# main.net
KiCad netlist of a schematic drawn in EAGLE
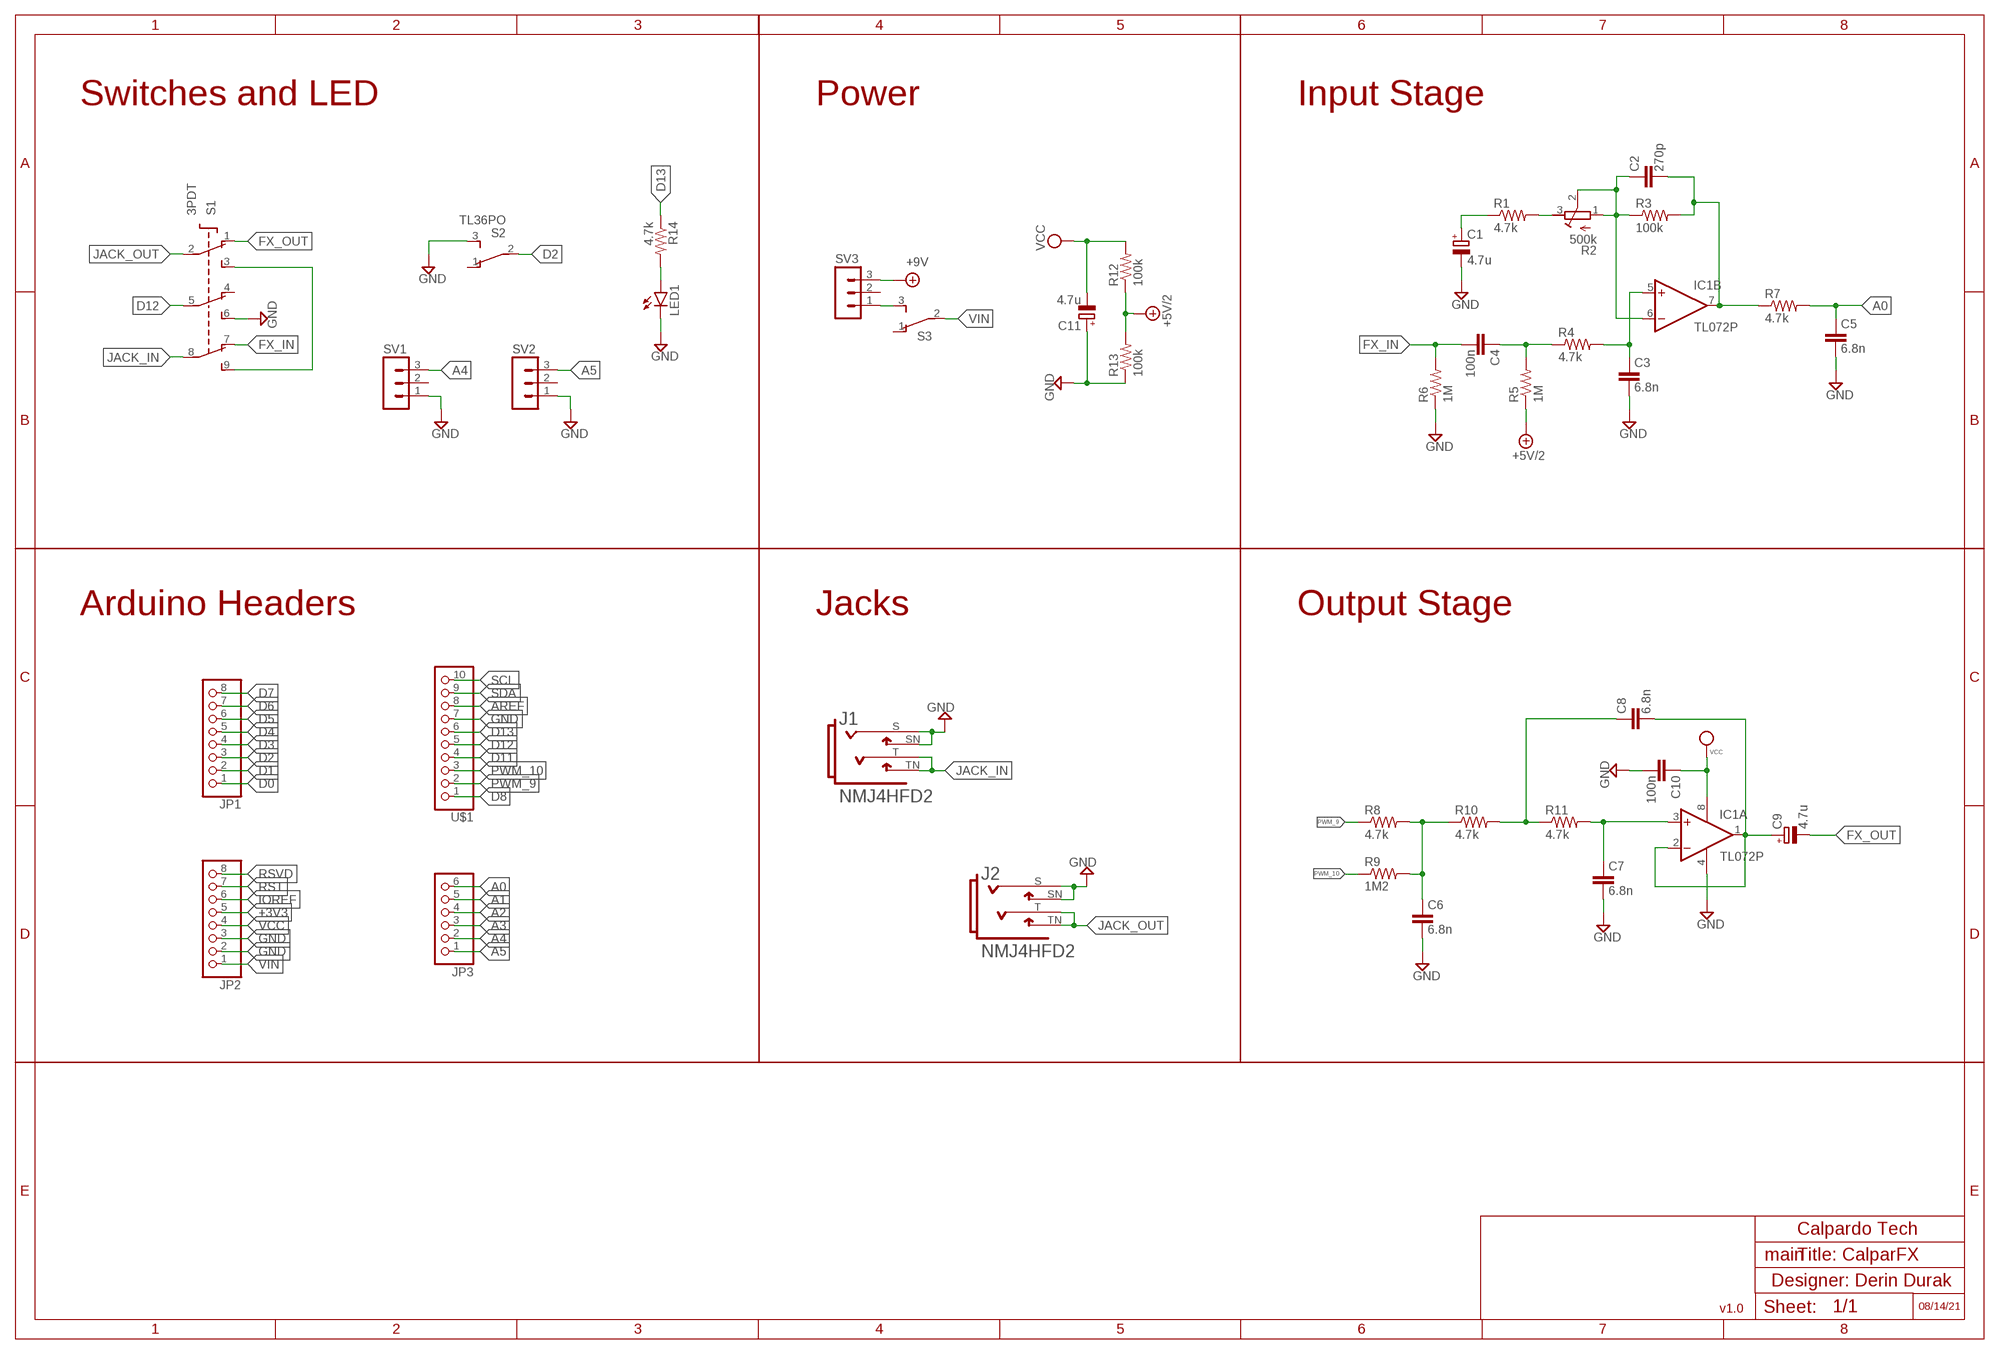
[diagram p0: schematic, sheet 1]

(export (version "E")
  (design (tool "Eeschema 10.0.6"))
  (components
    (comp (ref "C1")
      (value "4.7u")
      (footprint "eagle-import:E2-5")
      (libsource (lib "eagle-import") (part "CPOL-EUE2-5"))
    )
    (comp (ref "C2")
      (value "270p")
      (footprint "eagle-import:C025-024X044")
      (libsource (lib "eagle-import") (part "C-EU025-024X044"))
    )
    (comp (ref "C3")
      (value "6.8n")
      (footprint "eagle-import:C025-024X044")
      (libsource (lib "eagle-import") (part "C-EU025-024X044"))
    )
    (comp (ref "C4")
      (value "100n")
      (footprint "eagle-import:C025-024X044")
      (libsource (lib "eagle-import") (part "C-EU025-024X044"))
    )
    (comp (ref "C5")
      (value "6.8n")
      (footprint "eagle-import:C025-024X044")
      (libsource (lib "eagle-import") (part "C-EU025-024X044"))
    )
    (comp (ref "C6")
      (value "6.8n")
      (footprint "eagle-import:C025-024X044")
      (libsource (lib "eagle-import") (part "C-EU025-024X044"))
    )
    (comp (ref "C7")
      (value "6.8n")
      (footprint "eagle-import:C025-024X044")
      (libsource (lib "eagle-import") (part "C-EU025-024X044"))
    )
    (comp (ref "C8")
      (value "6.8n")
      (footprint "eagle-import:C025-024X044")
      (libsource (lib "eagle-import") (part "C-EU025-024X044"))
    )
    (comp (ref "C9")
      (value "4.7u")
      (footprint "eagle-import:E2-5")
      (libsource (lib "eagle-import") (part "CPOL-EUE2-5"))
    )
    (comp (ref "C10")
      (value "100n")
      (footprint "eagle-import:C025-024X044")
      (libsource (lib "eagle-import") (part "C-EU025-024X044"))
    )
    (comp (ref "C11")
      (value "4.7u")
      (footprint "eagle-import:E2-5")
      (libsource (lib "eagle-import") (part "CPOL-EUE2-5"))
    )
    (comp (ref "IC1")
      (value "TL072P")
      (footprint "eagle-import:DIL08")
      (libsource (lib "eagle-import") (part "TL072P"))
    )
    (comp (ref "J1")
      (value "NEUTRIK_NMJ4HFD2NEUTRIK_NMJ4HFD2_0_0")
      (footprint "eagle-import:NEUTRIK_NMJ4HFD2_0")
      (fields
        (field (name "MF") "Neutrik")
        (field (name "MOUSER_PART_NUMBER") "550-10201")
        (field (name "MPN") "NMJ4HFD2")
      )
      (libsource (lib "eagle-import") (part "NEUTRIK_NMJ4HFD2NEUTRIK_NMJ4HFD2_0_0"))
    )
    (comp (ref "J2")
      (value "NEUTRIK_NMJ4HFD2NEUTRIK_NMJ4HFD2_0_0")
      (footprint "eagle-import:NEUTRIK_NMJ4HFD2_0")
      (fields
        (field (name "MF") "Neutrik")
        (field (name "MOUSER_PART_NUMBER") "550-10201")
        (field (name "MPN") "NMJ4HFD2")
      )
      (libsource (lib "eagle-import") (part "NEUTRIK_NMJ4HFD2NEUTRIK_NMJ4HFD2_0_0"))
    )
    (comp (ref "JP1")
      (value "PINHD-1X8BIG")
      (footprint "eagle-import:1X08-BIG")
      (libsource (lib "eagle-import") (part "PINHD-1X8BIG"))
    )
    (comp (ref "JP2")
      (value "PINHD-1X8BIG")
      (footprint "eagle-import:1X08-BIG")
      (libsource (lib "eagle-import") (part "PINHD-1X8BIG"))
    )
    (comp (ref "JP3")
      (value "PINHD-1X6B")
      (footprint "eagle-import:1X06-BIG")
      (libsource (lib "eagle-import") (part "PINHD-1X6B"))
    )
    (comp (ref "LED1")
      (value "LED5MM")
      (footprint "eagle-import:LED5MM")
      (libsource (lib "eagle-import") (part "LED5MM"))
    )
    (comp (ref "R1")
      (value "4.7k")
      (footprint "eagle-import:0204_5")
      (libsource (lib "eagle-import") (part "R-US_0204/5"))
    )
    (comp (ref "R2")
      (value "500k")
      (footprint "eagle-import:RTRIM3296W")
      (libsource (lib "eagle-import") (part "R-TRIMM3296W"))
    )
    (comp (ref "R3")
      (value "100k")
      (footprint "eagle-import:0204_5")
      (libsource (lib "eagle-import") (part "R-US_0204/5"))
    )
    (comp (ref "R4")
      (value "4.7k")
      (footprint "eagle-import:0204_5")
      (libsource (lib "eagle-import") (part "R-US_0204/5"))
    )
    (comp (ref "R5")
      (value "1M")
      (footprint "eagle-import:0204_5")
      (libsource (lib "eagle-import") (part "R-US_0204/5"))
    )
    (comp (ref "R6")
      (value "1M")
      (footprint "eagle-import:0204_5")
      (libsource (lib "eagle-import") (part "R-US_0204/5"))
    )
    (comp (ref "R7")
      (value "4.7k")
      (footprint "eagle-import:0204_5")
      (libsource (lib "eagle-import") (part "R-US_0204/5"))
    )
    (comp (ref "R8")
      (value "4.7k")
      (footprint "eagle-import:0204_5")
      (libsource (lib "eagle-import") (part "R-US_0204/5"))
    )
    (comp (ref "R9")
      (value "1M2")
      (footprint "eagle-import:0204_5")
      (libsource (lib "eagle-import") (part "R-US_0204/5"))
    )
    (comp (ref "R10")
      (value "4.7k")
      (footprint "eagle-import:0204_5")
      (libsource (lib "eagle-import") (part "R-US_0204/5"))
    )
    (comp (ref "R11")
      (value "4.7k")
      (footprint "eagle-import:0204_5")
      (libsource (lib "eagle-import") (part "R-US_0204/5"))
    )
    (comp (ref "R12")
      (value "100k")
      (footprint "eagle-import:0204_5")
      (libsource (lib "eagle-import") (part "R-US_0204/5"))
    )
    (comp (ref "R13")
      (value "100k")
      (footprint "eagle-import:0204_5")
      (libsource (lib "eagle-import") (part "R-US_0204/5"))
    )
    (comp (ref "R14")
      (value "4.7k")
      (footprint "eagle-import:0204_5")
      (libsource (lib "eagle-import") (part "R-US_0204/5"))
    )
    (comp (ref "S1")
      (value "3PDT")
      (footprint "eagle-import:3PDT")
      (libsource (lib "eagle-import") (part "3PDT"))
    )
    (comp (ref "S2")
      (value "TL36PO")
      (footprint "eagle-import:TL3XPO")
      (libsource (lib "eagle-import") (part "TL36PO"))
    )
    (comp (ref "S3")
      (value "TL36PO")
      (footprint "eagle-import:TL3XPO")
      (libsource (lib "eagle-import") (part "TL36PO"))
    )
    (comp (ref "SV1")
      (value "MA03-1")
      (footprint "eagle-import:MA03-1")
      (libsource (lib "eagle-import") (part "MA03-1"))
    )
    (comp (ref "SV2")
      (value "MA03-1")
      (footprint "eagle-import:MA03-1")
      (libsource (lib "eagle-import") (part "MA03-1"))
    )
    (comp (ref "SV3")
      (value "MA03-1")
      (footprint "eagle-import:MA03-1")
      (libsource (lib "eagle-import") (part "MA03-1"))
    )
    (comp (ref "U$1")
      (value "PINHD-1X10")
      (footprint "eagle-import:1X10-BIG")
      (libsource (lib "eagle-import") (part "PINHD-1X10"))
    )
  )
  (nets
    (net (code "1") (name "+3V3") (class "Default")
      (node (ref "JP2") (pin "5") (pinfunction "5_5") (pintype "passive"))
    )
    (net (code "2") (name "+5V{slash}2") (class "Default")
      (node (ref "R12") (pin "1") (pinfunction "1_1") (pintype "passive"))
      (node (ref "R13") (pin "2") (pinfunction "2_2") (pintype "passive"))
      (node (ref "R5") (pin "1") (pinfunction "1_1") (pintype "passive"))
    )
    (net (code "3") (name "+9V") (class "Default")
      (node (ref "SV3") (pin "3") (pinfunction "3_3") (pintype "passive"))
    )
    (net (code "4") (name "A0") (class "Default")
      (node (ref "C5") (pin "1") (pinfunction "1_1") (pintype "passive"))
      (node (ref "JP3") (pin "6") (pinfunction "6_6") (pintype "passive"))
      (node (ref "R7") (pin "2") (pinfunction "2_2") (pintype "passive"))
    )
    (net (code "5") (name "A1") (class "Default")
      (node (ref "JP3") (pin "5") (pinfunction "5_5") (pintype "passive"))
    )
    (net (code "6") (name "A2") (class "Default")
      (node (ref "JP3") (pin "4") (pinfunction "4_4") (pintype "passive"))
    )
    (net (code "7") (name "A3") (class "Default")
      (node (ref "JP3") (pin "3") (pinfunction "3_3") (pintype "passive"))
    )
    (net (code "8") (name "A4") (class "Default")
      (node (ref "JP3") (pin "2") (pinfunction "2_2") (pintype "passive"))
      (node (ref "SV1") (pin "3") (pinfunction "3_3") (pintype "passive"))
    )
    (net (code "9") (name "A5") (class "Default")
      (node (ref "JP3") (pin "1") (pinfunction "1_1") (pintype "passive"))
      (node (ref "SV2") (pin "3") (pinfunction "3_3") (pintype "passive"))
    )
    (net (code "10") (name "AREF") (class "Default")
      (node (ref "U$1") (pin "8") (pinfunction "8_8") (pintype "passive"))
    )
    (net (code "11") (name "D0") (class "Default")
      (node (ref "JP1") (pin "1") (pinfunction "1_1") (pintype "passive"))
    )
    (net (code "12") (name "D1") (class "Default")
      (node (ref "JP1") (pin "2") (pinfunction "2_2") (pintype "passive"))
    )
    (net (code "13") (name "D2") (class "Default")
      (node (ref "JP1") (pin "3") (pinfunction "3_3") (pintype "passive"))
      (node (ref "S2") (pin "2") (pinfunction "P_2") (pintype "passive"))
    )
    (net (code "14") (name "D3") (class "Default")
      (node (ref "JP1") (pin "4") (pinfunction "4_4") (pintype "passive"))
    )
    (net (code "15") (name "D4") (class "Default")
      (node (ref "JP1") (pin "5") (pinfunction "5_5") (pintype "passive"))
    )
    (net (code "16") (name "D5") (class "Default")
      (node (ref "JP1") (pin "6") (pinfunction "6_6") (pintype "passive"))
    )
    (net (code "17") (name "D6") (class "Default")
      (node (ref "JP1") (pin "7") (pinfunction "7_7") (pintype "passive"))
    )
    (net (code "18") (name "D7") (class "Default")
      (node (ref "JP1") (pin "8") (pinfunction "8_8") (pintype "passive"))
    )
    (net (code "19") (name "D8") (class "Default")
      (node (ref "U$1") (pin "1") (pinfunction "1_1") (pintype "passive"))
    )
    (net (code "20") (name "D11") (class "Default")
      (node (ref "U$1") (pin "4") (pinfunction "4_4") (pintype "passive"))
    )
    (net (code "21") (name "D12") (class "Default")
      (node (ref "S1") (pin "5") (pinfunction "P2_5") (pintype "passive"))
      (node (ref "U$1") (pin "5") (pinfunction "5_5") (pintype "passive"))
    )
    (net (code "22") (name "D13") (class "Default")
      (node (ref "R14") (pin "1") (pinfunction "1_1") (pintype "passive"))
      (node (ref "U$1") (pin "6") (pinfunction "6_6") (pintype "passive"))
    )
    (net (code "23") (name "FX_IN") (class "Default")
      (node (ref "C4") (pin "2") (pinfunction "2_2") (pintype "passive"))
      (node (ref "R6") (pin "2") (pinfunction "2_2") (pintype "passive"))
      (node (ref "S1") (pin "7") (pinfunction "O3_7") (pintype "passive"))
    )
    (net (code "24") (name "FX_OUT") (class "Default")
      (node (ref "C9") (pin "-") (pinfunction "-_-") (pintype "passive"))
      (node (ref "S1") (pin "1") (pinfunction "O1_1") (pintype "passive"))
    )
    (net (code "25") (name "GND") (class "Default")
      (node (ref "C1") (pin "-") (pinfunction "-_-") (pintype "passive"))
      (node (ref "C10") (pin "2") (pinfunction "2_2") (pintype "passive"))
      (node (ref "C11") (pin "+") (pinfunction "+_+") (pintype "passive"))
      (node (ref "C3") (pin "2") (pinfunction "2_2") (pintype "passive"))
      (node (ref "C5") (pin "2") (pinfunction "2_2") (pintype "passive"))
      (node (ref "C6") (pin "2") (pinfunction "2_2") (pintype "passive"))
      (node (ref "C7") (pin "2") (pinfunction "2_2") (pintype "passive"))
      (node (ref "IC1") (pin "4") (pinfunction "V-_4") (pintype "power_in"))
      (node (ref "J1") (pin "S") (pinfunction "S_S") (pintype "passive"))
      (node (ref "J1") (pin "SN") (pinfunction "SN_SN") (pintype "passive"))
      (node (ref "J2") (pin "S") (pinfunction "S_S") (pintype "passive"))
      (node (ref "J2") (pin "SN") (pinfunction "SN_SN") (pintype "passive"))
      (node (ref "JP2") (pin "2") (pinfunction "2_2") (pintype "passive"))
      (node (ref "JP2") (pin "3") (pinfunction "3_3") (pintype "passive"))
      (node (ref "LED1") (pin "K") (pinfunction "C_K") (pintype "passive"))
      (node (ref "R13") (pin "1") (pinfunction "1_1") (pintype "passive"))
      (node (ref "R6") (pin "1") (pinfunction "1_1") (pintype "passive"))
      (node (ref "S1") (pin "6") (pinfunction "S2_6") (pintype "passive"))
      (node (ref "S2") (pin "3") (pinfunction "S_3") (pintype "passive"))
      (node (ref "SV1") (pin "1") (pinfunction "1_1") (pintype "passive"))
      (node (ref "SV2") (pin "1") (pinfunction "1_1") (pintype "passive"))
      (node (ref "U$1") (pin "7") (pinfunction "7_7") (pintype "passive"))
    )
    (net (code "26") (name "IOREF") (class "Default")
      (node (ref "JP2") (pin "6") (pinfunction "6_6") (pintype "passive"))
    )
    (net (code "27") (name "JACK_IN") (class "Default")
      (node (ref "J1") (pin "T") (pinfunction "T_T") (pintype "passive"))
      (node (ref "J1") (pin "TN") (pinfunction "TN_TN") (pintype "passive"))
      (node (ref "S1") (pin "8") (pinfunction "P3_8") (pintype "passive"))
    )
    (net (code "28") (name "JACK_OUT") (class "Default")
      (node (ref "J2") (pin "T") (pinfunction "T_T") (pintype "passive"))
      (node (ref "J2") (pin "TN") (pinfunction "TN_TN") (pintype "passive"))
      (node (ref "S1") (pin "2") (pinfunction "P1_2") (pintype "passive"))
    )
    (net (code "29") (name "Net-(C1-Pad+)") (class "Default")
      (node (ref "C1") (pin "+") (pinfunction "+_+") (pintype "passive"))
      (node (ref "R1") (pin "1") (pinfunction "1_1") (pintype "passive"))
    )
    (net (code "30") (name "Net-(C4-Pad1)") (class "Default")
      (node (ref "C4") (pin "1") (pinfunction "1_1") (pintype "passive"))
      (node (ref "R4") (pin "1") (pinfunction "1_1") (pintype "passive"))
      (node (ref "R5") (pin "2") (pinfunction "2_2") (pintype "passive"))
    )
    (net (code "31") (name "Net-(C6-Pad1)") (class "Default")
      (node (ref "C6") (pin "1") (pinfunction "1_1") (pintype "passive"))
      (node (ref "R10") (pin "1") (pinfunction "1_1") (pintype "passive"))
      (node (ref "R8") (pin "2") (pinfunction "2_2") (pintype "passive"))
      (node (ref "R9") (pin "2") (pinfunction "2_2") (pintype "passive"))
    )
    (net (code "32") (name "Net-(C8-Pad1)") (class "Default")
      (node (ref "C8") (pin "1") (pinfunction "1_1") (pintype "passive"))
      (node (ref "R10") (pin "2") (pinfunction "2_2") (pintype "passive"))
      (node (ref "R11") (pin "1") (pinfunction "1_1") (pintype "passive"))
    )
    (net (code "33") (name "Net-(IC1A-+IN)") (class "Default")
      (node (ref "C7") (pin "1") (pinfunction "1_1") (pintype "passive"))
      (node (ref "IC1") (pin "3") (pinfunction "+IN_3") (pintype "input"))
      (node (ref "R11") (pin "2") (pinfunction "2_2") (pintype "passive"))
    )
    (net (code "34") (name "Net-(IC1A--IN)") (class "Default")
      (node (ref "C8") (pin "2") (pinfunction "2_2") (pintype "passive"))
      (node (ref "C9") (pin "+") (pinfunction "+_+") (pintype "passive"))
      (node (ref "IC1") (pin "1") (pinfunction "OUT_1") (pintype "output"))
      (node (ref "IC1") (pin "2") (pinfunction "-IN_2") (pintype "input"))
    )
    (net (code "35") (name "Net-(IC1B-+IN)") (class "Default")
      (node (ref "C3") (pin "1") (pinfunction "1_1") (pintype "passive"))
      (node (ref "IC1") (pin "5") (pinfunction "+IN_5") (pintype "input"))
      (node (ref "R4") (pin "2") (pinfunction "2_2") (pintype "passive"))
    )
    (net (code "36") (name "Net-(IC1B--IN)") (class "Default")
      (node (ref "C2") (pin "1") (pinfunction "1_1") (pintype "passive"))
      (node (ref "IC1") (pin "6") (pinfunction "-IN_6") (pintype "input"))
      (node (ref "R2") (pin "1") (pinfunction "A_1") (pintype "passive"))
      (node (ref "R2") (pin "2") (pinfunction "S_2") (pintype "passive"))
      (node (ref "R3") (pin "1") (pinfunction "1_1") (pintype "passive"))
    )
    (net (code "37") (name "Net-(IC1B-OUT)") (class "Default")
      (node (ref "C2") (pin "2") (pinfunction "2_2") (pintype "passive"))
      (node (ref "IC1") (pin "7") (pinfunction "OUT_7") (pintype "output"))
      (node (ref "R3") (pin "2") (pinfunction "2_2") (pintype "passive"))
      (node (ref "R7") (pin "1") (pinfunction "1_1") (pintype "passive"))
    )
    (net (code "38") (name "Net-(LED1-PadA)") (class "Default")
      (node (ref "LED1") (pin "A") (pinfunction "A_A") (pintype "passive"))
      (node (ref "R14") (pin "2") (pinfunction "2_2") (pintype "passive"))
    )
    (net (code "39") (name "Net-(R2-E)") (class "Default")
      (node (ref "R1") (pin "2") (pinfunction "2_2") (pintype "passive"))
      (node (ref "R2") (pin "3") (pinfunction "E_3") (pintype "passive"))
    )
    (net (code "40") (name "Net-(S1-S1)") (class "Default")
      (node (ref "S1") (pin "3") (pinfunction "S1_3") (pintype "passive"))
      (node (ref "S1") (pin "9") (pinfunction "S3_9") (pintype "passive"))
    )
    (net (code "41") (name "Net-(S3-S)") (class "Default")
      (node (ref "S3") (pin "3") (pinfunction "S_3") (pintype "passive"))
      (node (ref "SV3") (pin "1") (pinfunction "1_1") (pintype "passive"))
    )
    (net (code "42") (name "PWM_9") (class "Default")
      (node (ref "R8") (pin "1") (pinfunction "1_1") (pintype "passive"))
      (node (ref "U$1") (pin "2") (pinfunction "2_2") (pintype "passive"))
    )
    (net (code "43") (name "PWM_10") (class "Default")
      (node (ref "R9") (pin "1") (pinfunction "1_1") (pintype "passive"))
      (node (ref "U$1") (pin "3") (pinfunction "3_3") (pintype "passive"))
    )
    (net (code "44") (name "RST") (class "Default")
      (node (ref "JP2") (pin "7") (pinfunction "7_7") (pintype "passive"))
    )
    (net (code "45") (name "RSVD") (class "Default")
      (node (ref "JP2") (pin "8") (pinfunction "8_8") (pintype "passive"))
    )
    (net (code "46") (name "SCL") (class "Default")
      (node (ref "U$1") (pin "10") (pinfunction "10_10") (pintype "passive"))
    )
    (net (code "47") (name "SDA") (class "Default")
      (node (ref "U$1") (pin "9") (pinfunction "9_9") (pintype "passive"))
    )
    (net (code "48") (name "VCC") (class "Default")
      (node (ref "C10") (pin "1") (pinfunction "1_1") (pintype "passive"))
      (node (ref "C11") (pin "-") (pinfunction "-_-") (pintype "passive"))
      (node (ref "IC1") (pin "8") (pinfunction "V+_8") (pintype "power_in"))
      (node (ref "JP2") (pin "4") (pinfunction "4_4") (pintype "passive"))
      (node (ref "R12") (pin "2") (pinfunction "2_2") (pintype "passive"))
    )
    (net (code "49") (name "VIN") (class "Default")
      (node (ref "JP2") (pin "1") (pinfunction "1_1") (pintype "passive"))
      (node (ref "S3") (pin "2") (pinfunction "P_2") (pintype "passive"))
    )
    (net (code "50") (name "unconnected-(S1-O2-Pad4)") (class "Default")
      (node (ref "S1") (pin "4") (pinfunction "O2_4") (pintype "passive"))
    )
    (net (code "51") (name "unconnected-(S2-O-Pad1)") (class "Default")
      (node (ref "S2") (pin "1") (pinfunction "O_1") (pintype "passive"))
    )
    (net (code "52") (name "unconnected-(S3-O-Pad1)") (class "Default")
      (node (ref "S3") (pin "1") (pinfunction "O_1") (pintype "passive"))
    )
    (net (code "53") (name "unconnected-(SV1-Pad2)") (class "Default")
      (node (ref "SV1") (pin "2") (pinfunction "2_2") (pintype "passive"))
    )
    (net (code "54") (name "unconnected-(SV2-Pad2)") (class "Default")
      (node (ref "SV2") (pin "2") (pinfunction "2_2") (pintype "passive"))
    )
    (net (code "55") (name "unconnected-(SV3-Pad2)") (class "Default")
      (node (ref "SV3") (pin "2") (pinfunction "2_2") (pintype "passive"))
    )
  )
)
